# Adafruit_MS8607.net
KiCad netlist of a schematic drawn in EAGLE
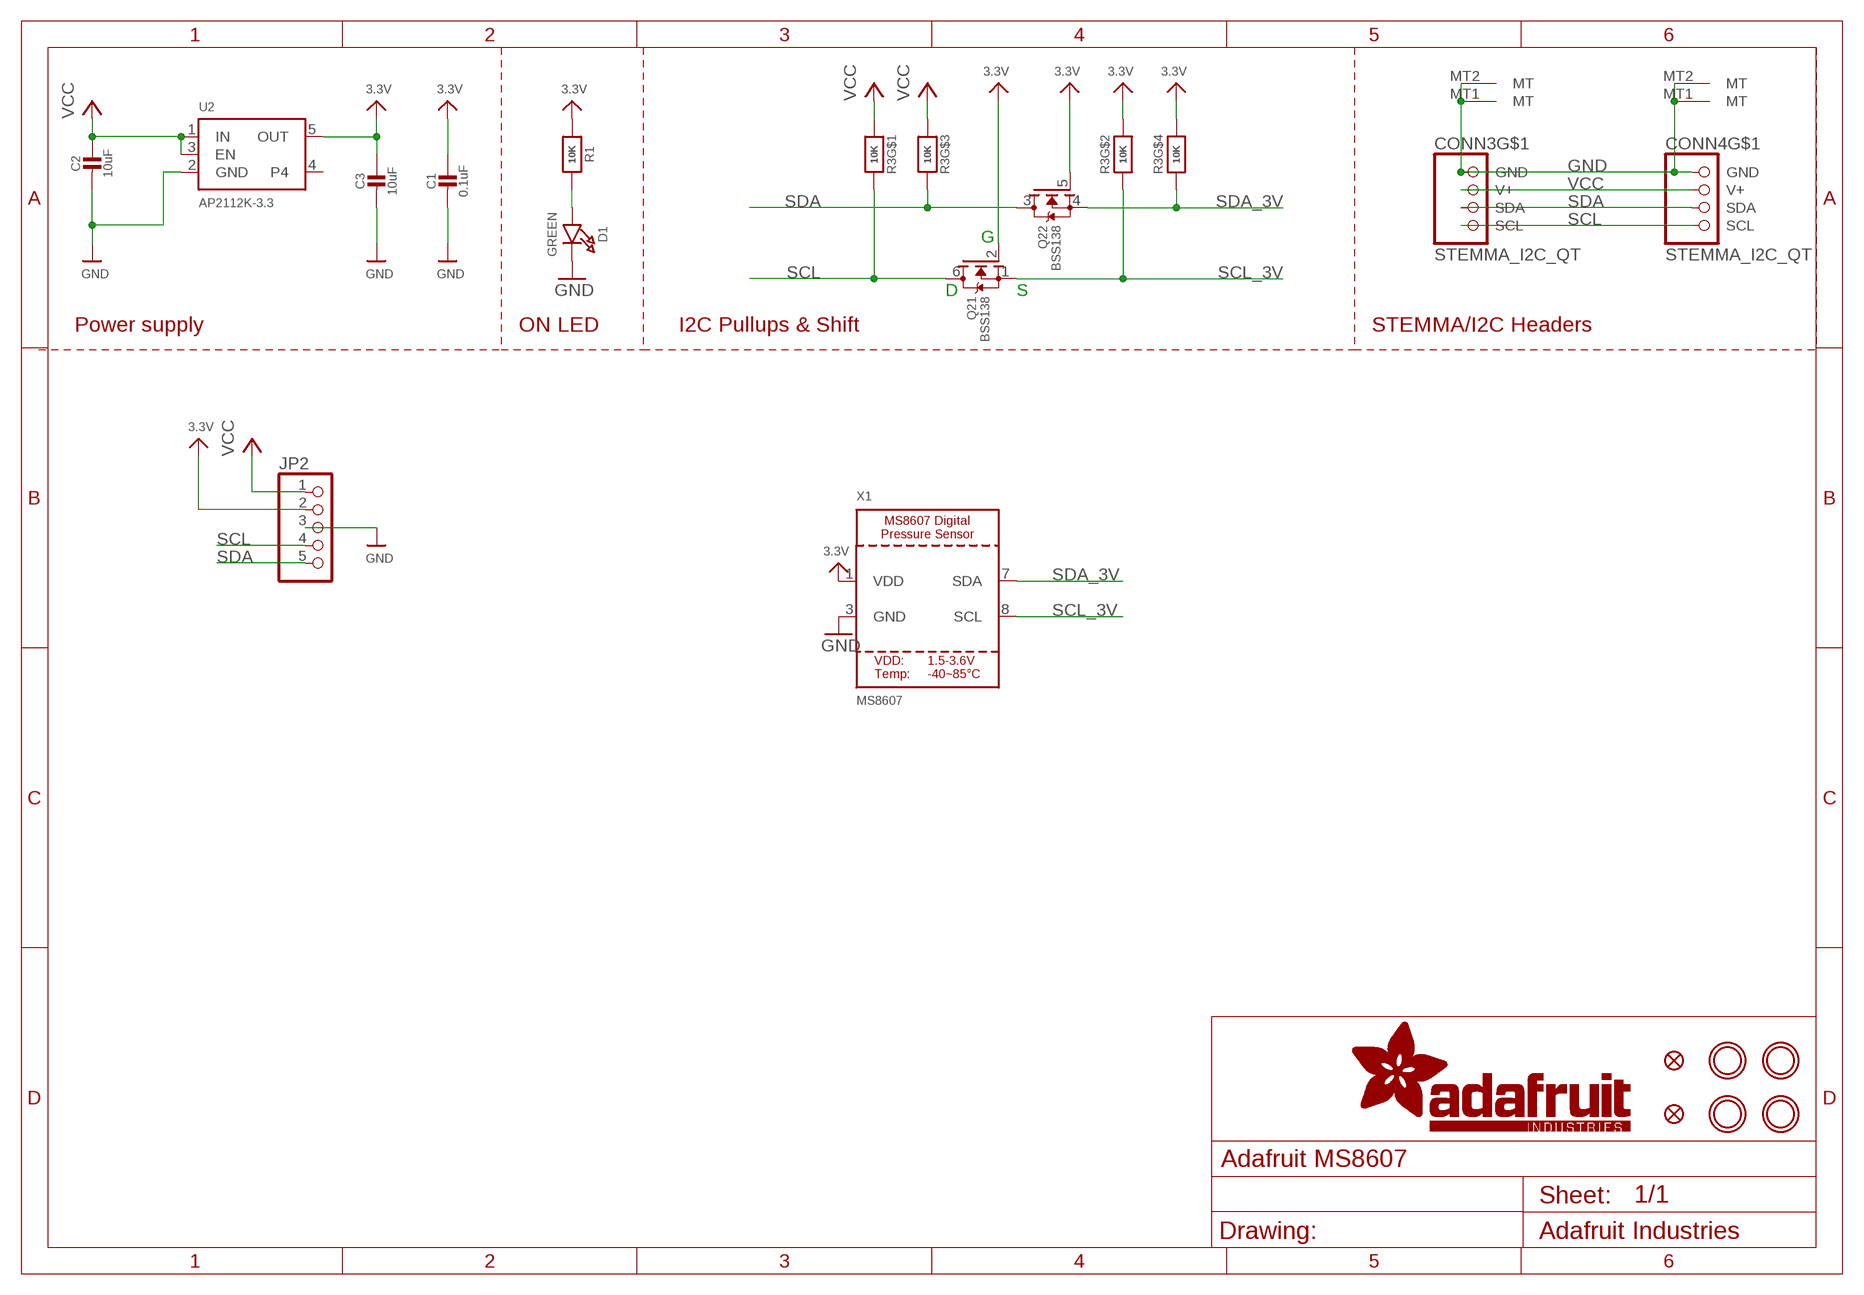
[diagram p0: schematic, sheet 1]

(export (version "E")
  (design (tool "Eeschema 10.0.6"))
  (components
    (comp (ref "C1")
      (value "0.1uF")
      (footprint "eagle-import:0603-NO")
      (libsource (lib "eagle-import") (part "CAP_CERAMIC0603_NO"))
    )
    (comp (ref "C2")
      (value "10uF")
      (footprint "eagle-import:0805-NO")
      (libsource (lib "eagle-import") (part "CAP_CERAMIC0805-NOOUTLINE"))
    )
    (comp (ref "C3")
      (value "10uF")
      (footprint "eagle-import:0805-NO")
      (libsource (lib "eagle-import") (part "CAP_CERAMIC0805-NOOUTLINE"))
    )
    (comp (ref "CONN3")
      (value "STEMMA_I2C_QT")
      (footprint "eagle-import:JST_SH4")
      (libsource (lib "eagle-import") (part "STEMMA_I2C_QT"))
    )
    (comp (ref "CONN4")
      (value "STEMMA_I2C_QT")
      (footprint "eagle-import:JST_SH4")
      (libsource (lib "eagle-import") (part "STEMMA_I2C_QT"))
    )
    (comp (ref "D1")
      (value "GREEN")
      (footprint "eagle-import:CHIPLED_0603_NOOUTLINE")
      (libsource (lib "eagle-import") (part "LED0603_NOOUTLINE"))
    )
    (comp (ref "FID3")
      (value "FIDUCIAL_1MM")
      (footprint "eagle-import:FIDUCIAL_1MM")
      (libsource (lib "eagle-import") (part "FIDUCIAL_1MM"))
    )
    (comp (ref "FID4")
      (value "FIDUCIAL_1MM")
      (footprint "eagle-import:FIDUCIAL_1MM")
      (libsource (lib "eagle-import") (part "FIDUCIAL_1MM"))
    )
    (comp (ref "JP2")
      (value "HEADER-1X5ROUND")
      (footprint "eagle-import:1X05_ROUND")
      (libsource (lib "eagle-import") (part "HEADER-1X5ROUND"))
    )
    (comp (ref "Q2")
      (value "BSS138")
      (footprint "eagle-import:SOT363")
      (libsource (lib "eagle-import") (part "MOSFET-N_DUAL"))
    )
    (comp (ref "R1")
      (value "10K")
      (footprint "eagle-import:0603-NO")
      (libsource (lib "eagle-import") (part "RESISTOR_0603_NOOUT"))
    )
    (comp (ref "R3")
      (value "10K")
      (footprint "eagle-import:RESPACK_4X0603")
      (libsource (lib "eagle-import") (part "RESISTOR_4PACK"))
    )
    (comp (ref "U$1")
      (value "MOUNTINGHOLE2.5")
      (footprint "eagle-import:MOUNTINGHOLE_2.5_PLATED")
      (libsource (lib "eagle-import") (part "MOUNTINGHOLE2.5"))
    )
    (comp (ref "U$17")
      (value "MOUNTINGHOLE2.5")
      (footprint "eagle-import:MOUNTINGHOLE_2.5_PLATED")
      (libsource (lib "eagle-import") (part "MOUNTINGHOLE2.5"))
    )
    (comp (ref "U$19")
      (value "MOUNTINGHOLE2.5")
      (footprint "eagle-import:MOUNTINGHOLE_2.5_PLATED")
      (libsource (lib "eagle-import") (part "MOUNTINGHOLE2.5"))
    )
    (comp (ref "U$21")
      (value "MOUNTINGHOLE2.5")
      (footprint "eagle-import:MOUNTINGHOLE_2.5_PLATED")
      (libsource (lib "eagle-import") (part "MOUNTINGHOLE2.5"))
    )
    (comp (ref "U2")
      (value "AP2112K-3.3")
      (footprint "eagle-import:SOT23-5")
      (libsource (lib "eagle-import") (part "VREG_SOT23-5"))
    )
    (comp (ref "X1")
      (value "MS8607")
      (footprint "eagle-import:MS8607")
      (libsource (lib "eagle-import") (part "MS8607"))
    )
  )
  (nets
    (net (code "1") (name "/SCL") (class "Default")
      (node (ref "CONN3") (pin "4") (pinfunction "SCL_4") (pintype "passive"))
      (node (ref "CONN4") (pin "4") (pinfunction "SCL_4") (pintype "passive"))
      (node (ref "JP2") (pin "4") (pinfunction "4_4") (pintype "passive"))
      (node (ref "Q2") (pin "6") (pinfunction "D_6") (pintype "bidirectional"))
      (node (ref "R3") (pin "8") (pinfunction "2_8") (pintype "passive"))
    )
    (net (code "2") (name "/SCL_3V") (class "Default")
      (node (ref "Q2") (pin "1") (pinfunction "S_1") (pintype "bidirectional"))
      (node (ref "R3") (pin "7") (pinfunction "2_7") (pintype "passive"))
      (node (ref "X1") (pin "8") (pinfunction "SCL_8") (pintype "bidirectional"))
    )
    (net (code "3") (name "/SDA") (class "Default")
      (node (ref "CONN3") (pin "3") (pinfunction "SDA_3") (pintype "passive"))
      (node (ref "CONN4") (pin "3") (pinfunction "SDA_3") (pintype "passive"))
      (node (ref "JP2") (pin "5") (pinfunction "5_5") (pintype "passive"))
      (node (ref "Q2") (pin "3") (pinfunction "D_3") (pintype "bidirectional"))
      (node (ref "R3") (pin "6") (pinfunction "2_6") (pintype "passive"))
    )
    (net (code "4") (name "/SDA_3V") (class "Default")
      (node (ref "Q2") (pin "4") (pinfunction "S_4") (pintype "bidirectional"))
      (node (ref "R3") (pin "5") (pinfunction "2_5") (pintype "passive"))
      (node (ref "X1") (pin "7") (pinfunction "SDA_7") (pintype "bidirectional"))
    )
    (net (code "5") (name "3.3V") (class "Default")
      (node (ref "C1") (pin "1") (pinfunction "1_1") (pintype "passive"))
      (node (ref "C3") (pin "1") (pinfunction "1_1") (pintype "passive"))
      (node (ref "JP2") (pin "2") (pinfunction "2_2") (pintype "passive"))
      (node (ref "Q2") (pin "2") (pinfunction "G_2") (pintype "bidirectional"))
      (node (ref "Q2") (pin "5") (pinfunction "G_5") (pintype "bidirectional"))
      (node (ref "R1") (pin "1") (pinfunction "1_1") (pintype "passive"))
      (node (ref "R3") (pin "2") (pinfunction "1_2") (pintype "passive"))
      (node (ref "R3") (pin "4") (pinfunction "1_4") (pintype "passive"))
      (node (ref "U2") (pin "5") (pinfunction "OUT_5") (pintype "power_in"))
      (node (ref "X1") (pin "1") (pinfunction "VDD_1") (pintype "power_in"))
    )
    (net (code "6") (name "GND") (class "Default")
      (node (ref "C1") (pin "2") (pinfunction "2_2") (pintype "passive"))
      (node (ref "C2") (pin "2") (pinfunction "2_2") (pintype "passive"))
      (node (ref "C3") (pin "2") (pinfunction "2_2") (pintype "passive"))
      (node (ref "CONN3") (pin "1") (pinfunction "GND_1") (pintype "passive"))
      (node (ref "CONN3") (pin "MT1") (pinfunction "MT_MT1") (pintype "bidirectional"))
      (node (ref "CONN3") (pin "MT2") (pinfunction "MT_MT2") (pintype "bidirectional"))
      (node (ref "CONN4") (pin "1") (pinfunction "GND_1") (pintype "passive"))
      (node (ref "CONN4") (pin "MT1") (pinfunction "MT_MT1") (pintype "bidirectional"))
      (node (ref "CONN4") (pin "MT2") (pinfunction "MT_MT2") (pintype "bidirectional"))
      (node (ref "D1") (pin "C") (pinfunction "C_C") (pintype "passive"))
      (node (ref "JP2") (pin "3") (pinfunction "3_3") (pintype "passive"))
      (node (ref "U2") (pin "2") (pinfunction "GND_2") (pintype "power_in"))
      (node (ref "X1") (pin "3") (pinfunction "GND_3") (pintype "power_in"))
    )
    (net (code "7") (name "Net-(D1-PadA)") (class "Default")
      (node (ref "D1") (pin "A") (pinfunction "A_A") (pintype "passive"))
      (node (ref "R1") (pin "2") (pinfunction "2_2") (pintype "passive"))
    )
    (net (code "8") (name "VCC") (class "Default")
      (node (ref "C2") (pin "1") (pinfunction "1_1") (pintype "passive"))
      (node (ref "CONN3") (pin "2") (pinfunction "V+_2") (pintype "passive"))
      (node (ref "CONN4") (pin "2") (pinfunction "V+_2") (pintype "passive"))
      (node (ref "JP2") (pin "1") (pinfunction "1_1") (pintype "passive"))
      (node (ref "R3") (pin "1") (pinfunction "1_1") (pintype "passive"))
      (node (ref "R3") (pin "3") (pinfunction "1_3") (pintype "passive"))
      (node (ref "U2") (pin "1") (pinfunction "IN_1") (pintype "power_in"))
      (node (ref "U2") (pin "3") (pinfunction "EN_3") (pintype "input"))
    )
    (net (code "9") (name "unconnected-(U2-P4-Pad4)") (class "Default")
      (node (ref "U2") (pin "4") (pinfunction "P4_4") (pintype "bidirectional"))
    )
  )
)
